# Fonte_Variavel_Esquematico.net
KiCad netlist of a schematic drawn in EasyEDA
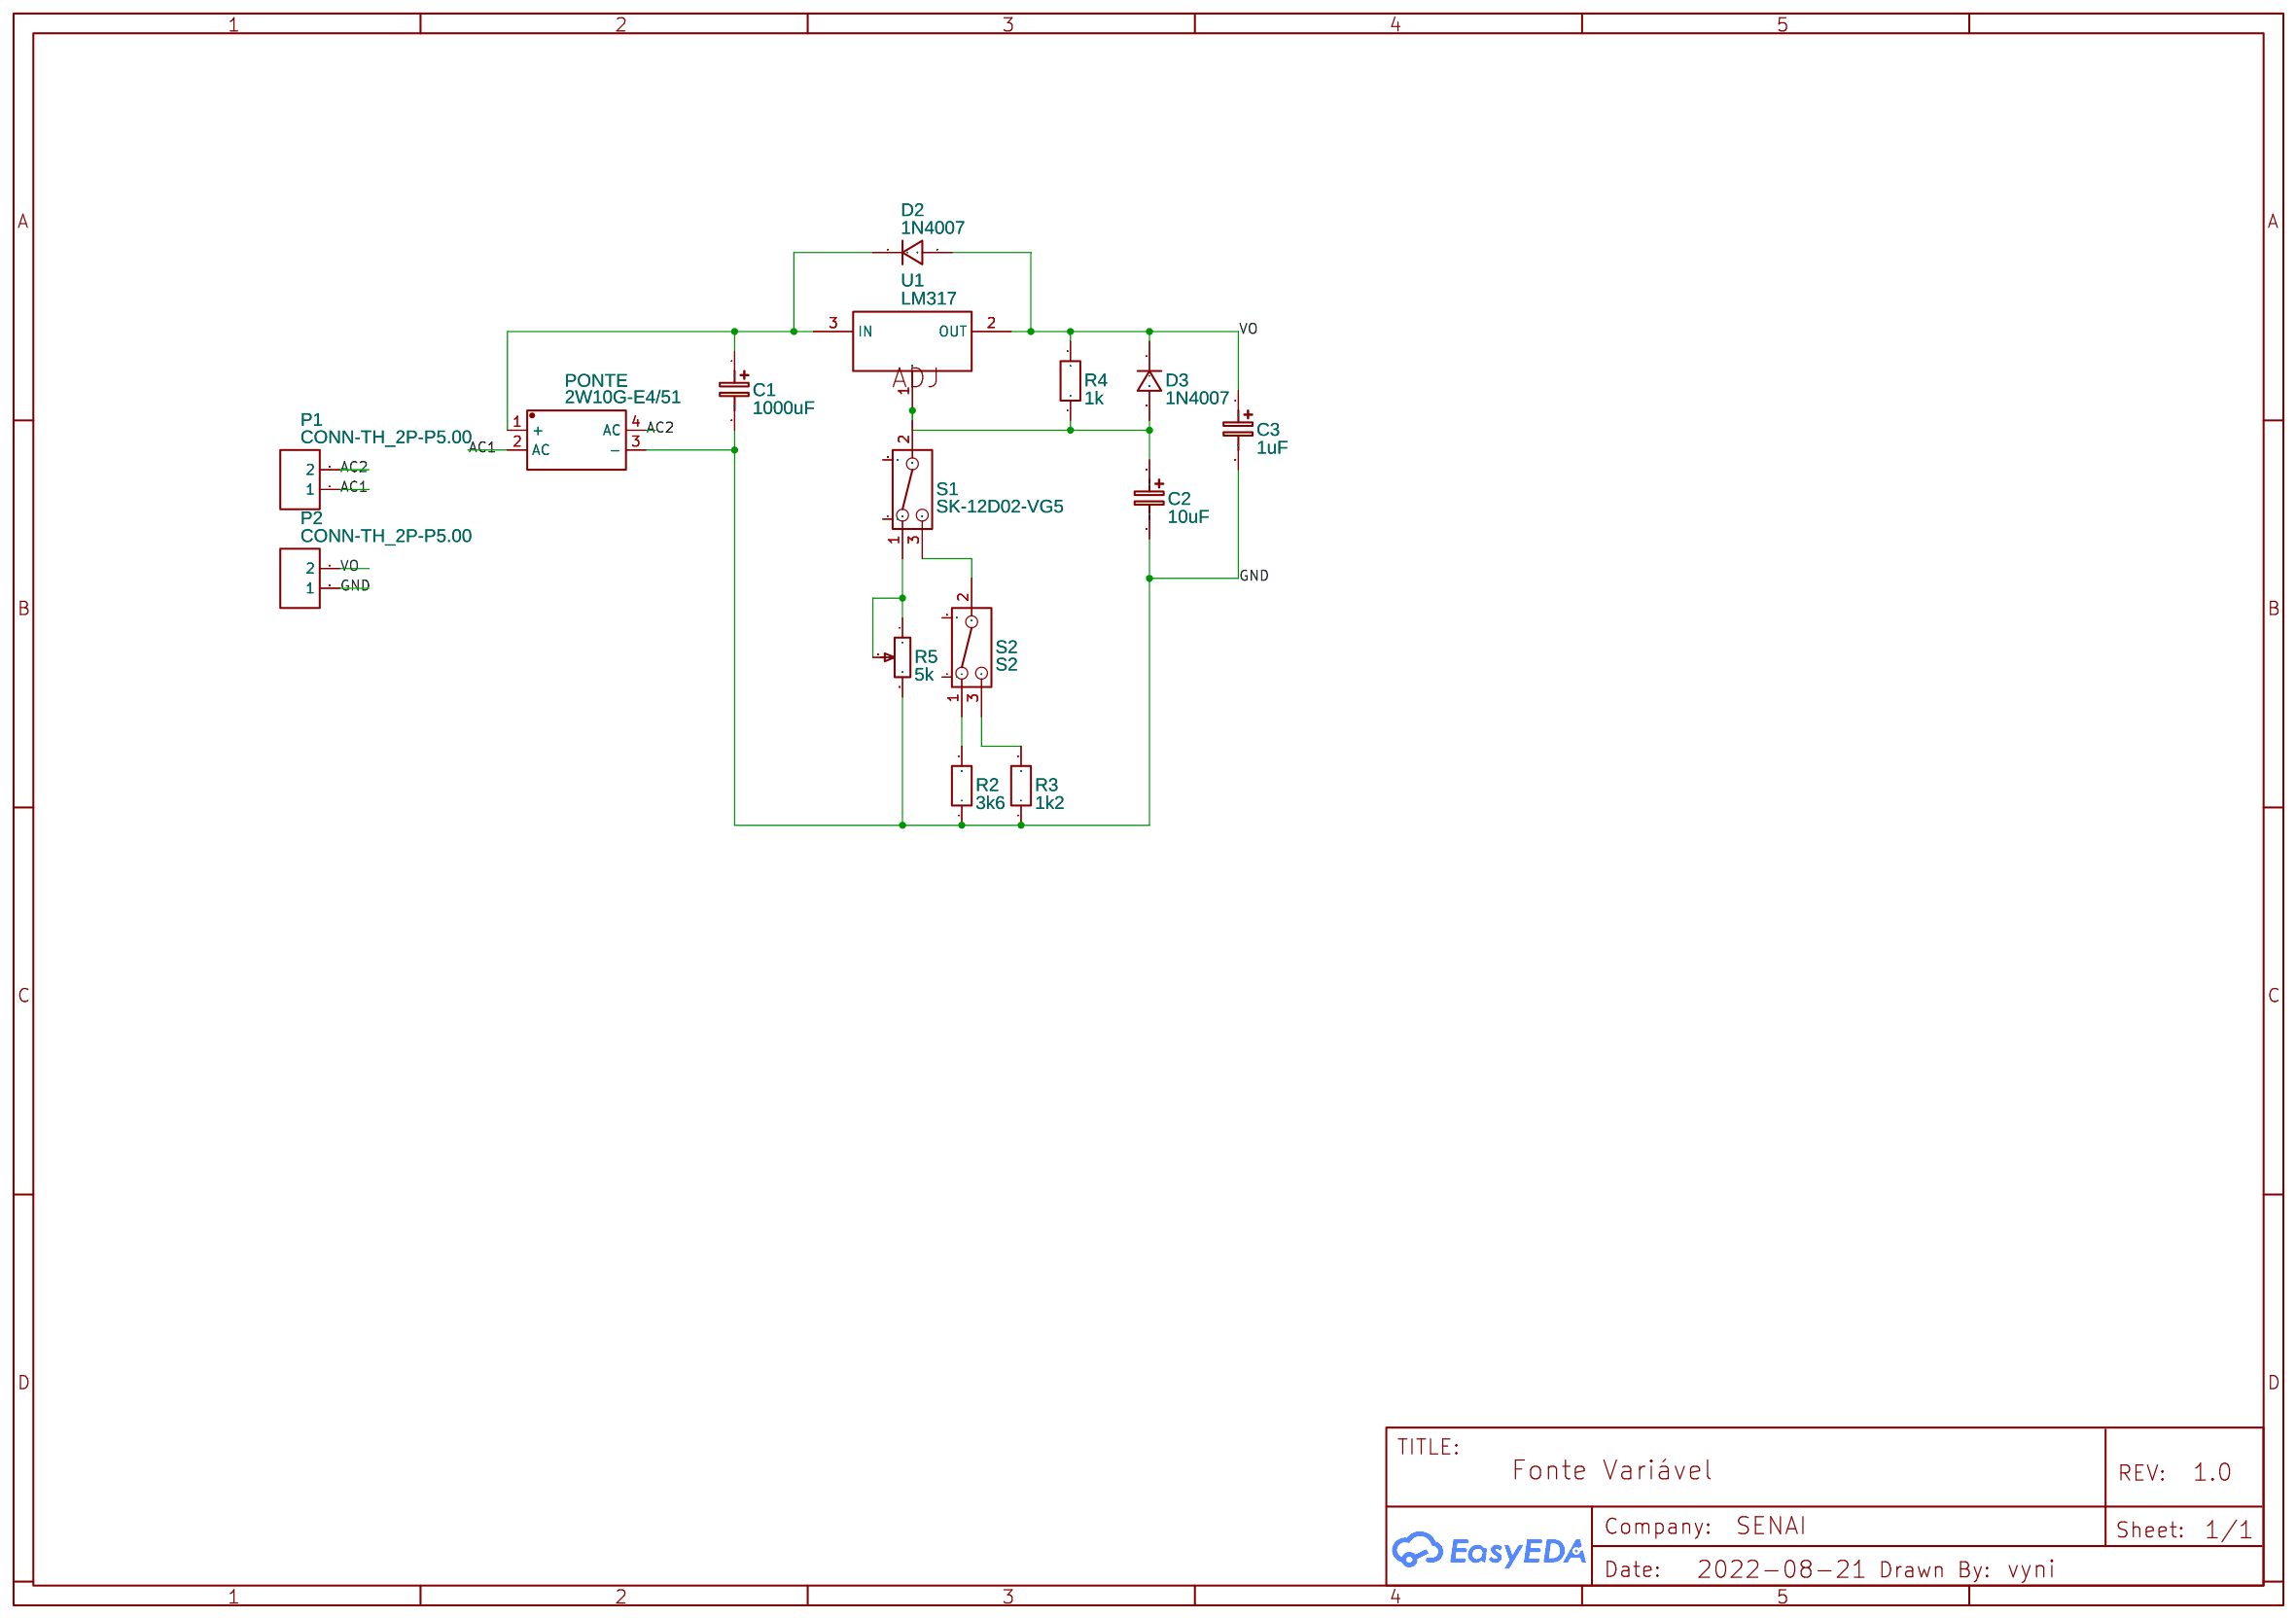
[diagram p0: schematic sheet]

(export (version "E")
  (design (tool "Eeschema 10.0.6"))
  (components
    (comp (ref "C1") (value "1000uF") (libsource (lib "") (part "CE_TH_D6.3×F2.5_EU_1")))
    (comp (ref "C2") (value "10uF") (libsource (lib "") (part "CE_TH_D6.3×F2.5_EU")))
    (comp (ref "C3") (value "1uF") (libsource (lib "") (part "CE_TH_D6.3×F2.5_EU")))
    (comp (ref "D2")
      (value "1N4007")
      (fields (field (name "BOM_Supplier Part") "C106903"))
      (libsource (lib "") (part "1N4007_1"))
    )
    (comp (ref "D3")
      (value "1N4007")
      (fields (field (name "BOM_Supplier Part") "C106903"))
      (libsource (lib "") (part "1N4007"))
    )
    (comp (ref "P1") (value "CONN-TH_2P-P5.00") (libsource (lib "") (part "CONN-TH_2P-P5.00")))
    (comp (ref "P2") (value "CONN-TH_2P-P5.00") (libsource (lib "") (part "CONN-TH_2P-P5.00")))
    (comp (ref "PONTE")
      (value "2W10G-E4/51")
      (fields (field (name "BOM_Supplier Part") "C266671"))
      (libsource (lib "") (part "2W10G-E4/51"))
    )
    (comp (ref "R2") (value "3k6") (libsource (lib "") (part "R_AXIAL-0.4_EU")))
    (comp (ref "R3") (value "1k2") (libsource (lib "") (part "R_AXIAL-0.4_EU")))
    (comp (ref "R4") (value "1k") (libsource (lib "") (part "R_AXIAL-0.4_EU")))
    (comp (ref "R5")
      (value "5k")
      (fields
        (field (name "BOM_Manufacturer Part") "3386P-1-101LF")
        (field (name "BOM_Supplier Part") "C125022")
      )
      (libsource (lib "") (part "PONTENCIOMETRO COPY COPY"))
    )
    (comp (ref "S1")
      (value "SK-12D02-VG5")
      (fields (field (name "BOM_Supplier Part") "C136722"))
      (libsource (lib "") (part "SK-12D02-VG5"))
    )
    (comp (ref "S2")
      (value "S2")
      (fields
        (field (name "BOM_Manufacturer Part") "SK-12D02-VG5")
        (field (name "BOM_Supplier Part") "C136722")
      )
      (libsource (lib "") (part "SK-12D02-VG5"))
    )
    (comp (ref "U1")
      (value "LM317")
      (fields
        (field (name "BOM_Manufacturer Part") "LM317LZ/LFT2")
        (field (name "BOM_Supplier Part") "C2877243")
      )
      (libsource (lib "") (part "LM317LZ/LFT2"))
    )
  )
  (nets
    (net (code "1") (name "/AC1") (class "Default")
      (node (ref "P1") (pin "1") (pinfunction "1_1") (pintype "unspecified"))
      (node (ref "PONTE") (pin "2") (pinfunction "AC_2") (pintype "unspecified"))
    )
    (net (code "2") (name "/AC2") (class "Default")
      (node (ref "P1") (pin "2") (pinfunction "2_2") (pintype "unspecified"))
      (node (ref "PONTE") (pin "4") (pinfunction "AC_4") (pintype "unspecified"))
    )
    (net (code "3") (name "/GND") (class "Default")
      (node (ref "C1") (pin "2") (pinfunction "2_2") (pintype "unspecified"))
      (node (ref "C2") (pin "2") (pinfunction "2_2") (pintype "unspecified"))
      (node (ref "C3") (pin "2") (pinfunction "2_2") (pintype "unspecified"))
      (node (ref "P2") (pin "1") (pinfunction "1_1") (pintype "unspecified"))
      (node (ref "PONTE") (pin "3") (pinfunction "-_3") (pintype "unspecified"))
      (node (ref "R2") (pin "1") (pinfunction "1_1") (pintype "unspecified"))
      (node (ref "R3") (pin "1") (pinfunction "1_1") (pintype "unspecified"))
      (node (ref "R5") (pin "3") (pinfunction "3_3") (pintype "input"))
    )
    (net (code "4") (name "/VO") (class "Default")
      (node (ref "C3") (pin "1") (pinfunction "1_1") (pintype "unspecified"))
      (node (ref "D2") (pin "2") (pinfunction "2_2") (pintype "unspecified"))
      (node (ref "D3") (pin "1") (pinfunction "1_1") (pintype "unspecified"))
      (node (ref "P2") (pin "2") (pinfunction "2_2") (pintype "unspecified"))
      (node (ref "R4") (pin "2") (pinfunction "2_2") (pintype "unspecified"))
      (node (ref "U1") (pin "2") (pinfunction "OUT_2") (pintype "passive"))
    )
    (net (code "5") (name "Net-(PONTE-+)") (class "Default")
      (node (ref "C1") (pin "1") (pinfunction "1_1") (pintype "unspecified"))
      (node (ref "D2") (pin "1") (pinfunction "1_1") (pintype "unspecified"))
      (node (ref "PONTE") (pin "1") (pinfunction "+_1") (pintype "unspecified"))
      (node (ref "U1") (pin "3") (pinfunction "IN_3") (pintype "passive"))
    )
    (net (code "6") (name "Net-(R2-Pad2)") (class "Default")
      (node (ref "R2") (pin "2") (pinfunction "2_2") (pintype "unspecified"))
      (node (ref "S2") (pin "1") (pinfunction "1_1") (pintype "unspecified"))
    )
    (net (code "7") (name "Net-(R3-Pad2)") (class "Default")
      (node (ref "R3") (pin "2") (pinfunction "2_2") (pintype "unspecified"))
      (node (ref "S2") (pin "3") (pinfunction "3_3") (pintype "unspecified"))
    )
    (net (code "8") (name "Net-(R5-Pad1)") (class "Default")
      (node (ref "R5") (pin "1") (pinfunction "1_1") (pintype "input"))
      (node (ref "R5") (pin "2") (pinfunction "2_2") (pintype "input"))
      (node (ref "S1") (pin "1") (pinfunction "1_1") (pintype "unspecified"))
    )
    (net (code "9") (name "Net-(S1-Pad3)") (class "Default")
      (node (ref "S1") (pin "3") (pinfunction "3_3") (pintype "unspecified"))
      (node (ref "S2") (pin "2") (pinfunction "2_2") (pintype "unspecified"))
    )
    (net (code "10") (name "Net-(U1-ADJ)") (class "Default")
      (node (ref "C2") (pin "1") (pinfunction "1_1") (pintype "unspecified"))
      (node (ref "D3") (pin "2") (pinfunction "2_2") (pintype "unspecified"))
      (node (ref "R4") (pin "1") (pinfunction "1_1") (pintype "unspecified"))
      (node (ref "S1") (pin "2") (pinfunction "2_2") (pintype "unspecified"))
      (node (ref "U1") (pin "1") (pinfunction "ADJ_1") (pintype "passive"))
    )
    (net (code "11") (name "unconnected-(S1-Pad4)") (class "Default")
      (node (ref "S1") (pin "4") (pinfunction "4_4") (pintype "unspecified"))
    )
    (net (code "12") (name "unconnected-(S1-Pad5)") (class "Default")
      (node (ref "S1") (pin "5") (pinfunction "5_5") (pintype "unspecified"))
    )
    (net (code "13") (name "unconnected-(S2-Pad4)") (class "Default")
      (node (ref "S2") (pin "4") (pinfunction "4_4") (pintype "unspecified"))
    )
    (net (code "14") (name "unconnected-(S2-Pad5)") (class "Default")
      (node (ref "S2") (pin "5") (pinfunction "5_5") (pintype "unspecified"))
    )
  )
)
